# LPC1114_--_Valdez_Mutant_v_03.net
KiCad netlist of a schematic drawn in EAGLE
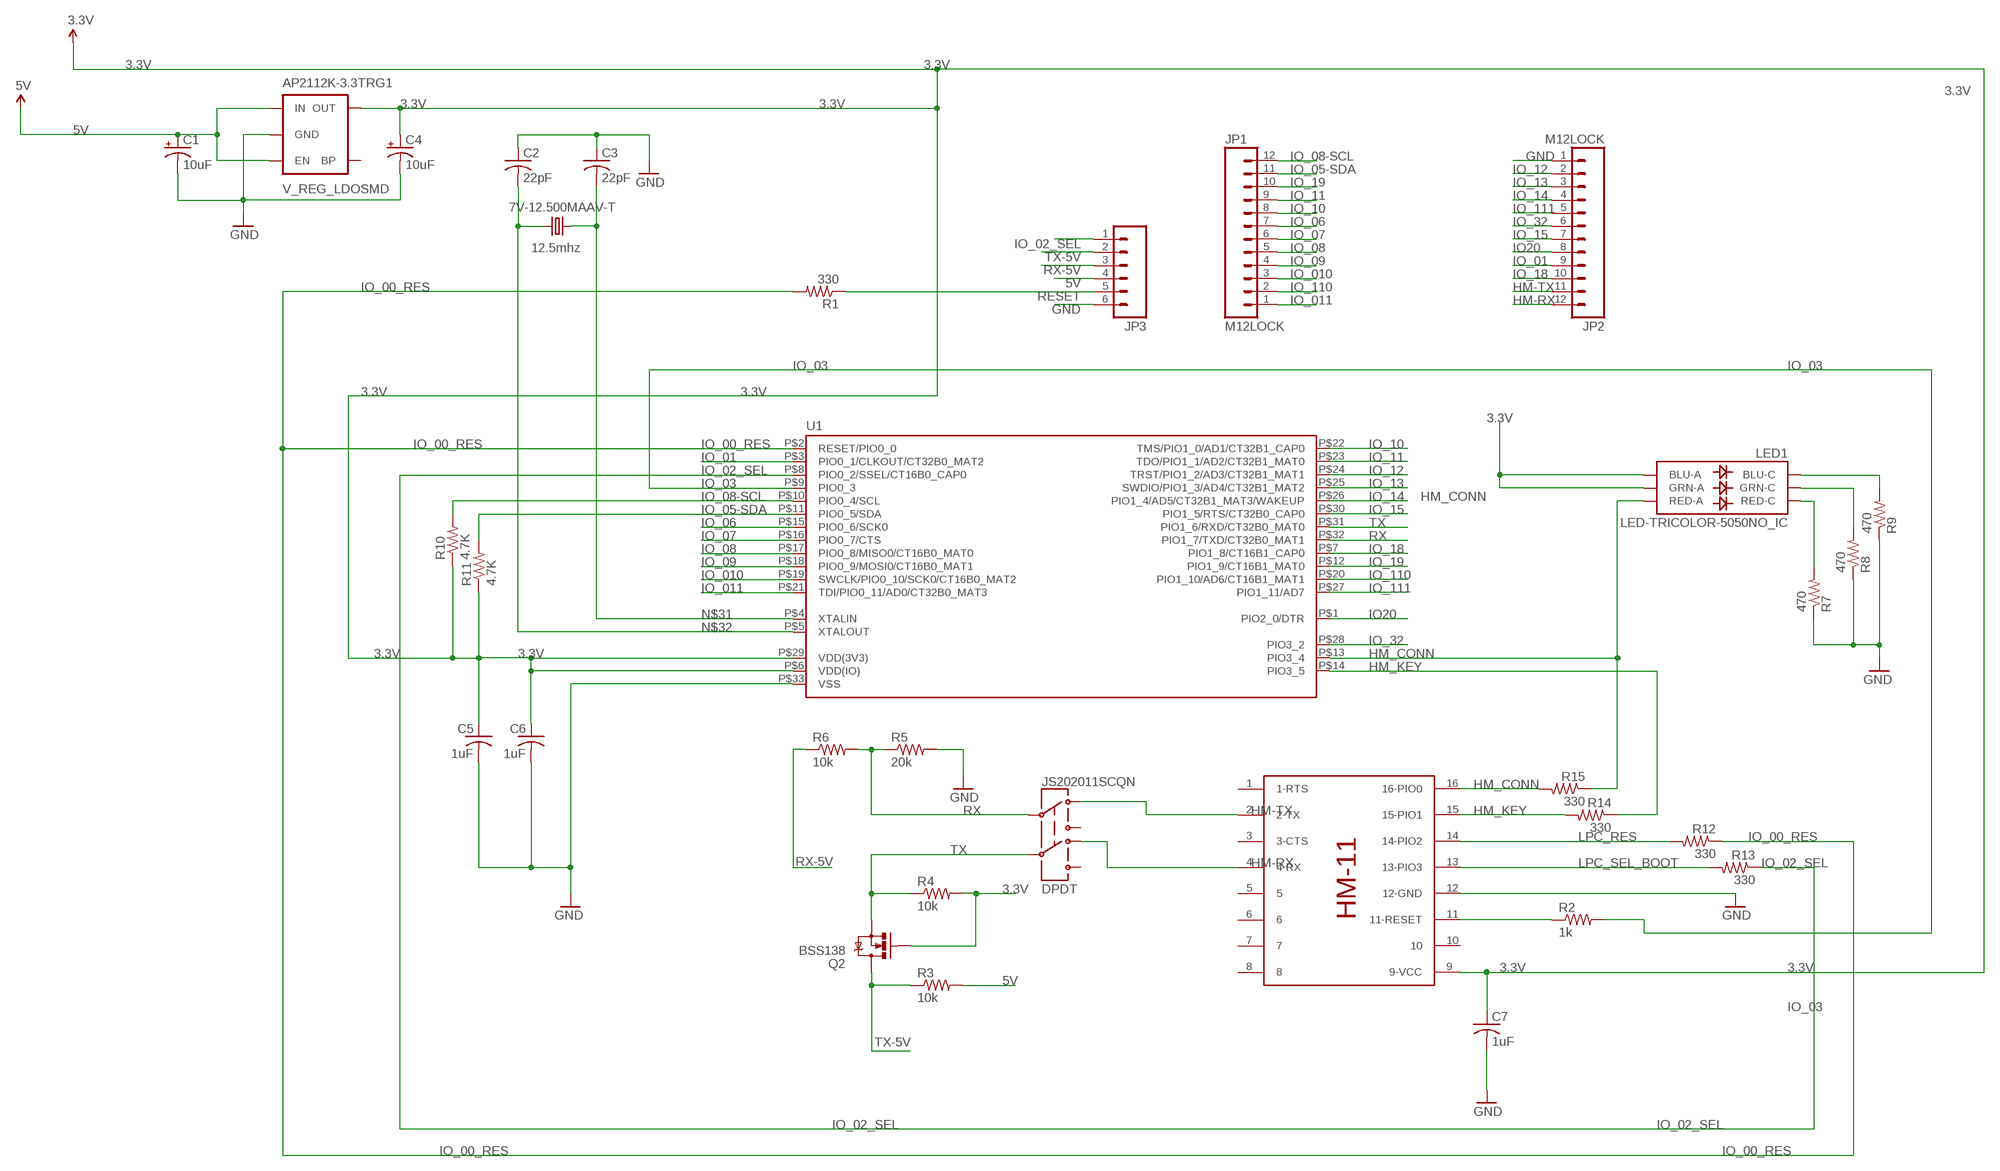
[diagram p0: schematic, sheet 1]

(export (version "E")
  (design (tool "Eeschema 10.0.6"))
  (components
    (comp (ref "7V-12.500MAAV-T")
      (value "12.5mhz")
      (footprint "eagle-import:CRYSTAL-SMD-5X3")
      (libsource (lib "eagle-import") (part "CRYSTAL5X3"))
    )
    (comp (ref "AP2112K-3.3TRG1")
      (value "V_REG_LDOSMD")
      (footprint "eagle-import:SOT23-5")
      (libsource (lib "eagle-import") (part "V_REG_LDOSMD"))
    )
    (comp (ref "C1")
      (value "10uF")
      (footprint "eagle-import:EIA3216")
      (libsource (lib "eagle-import") (part "CAP_POL1206"))
    )
    (comp (ref "C2")
      (value "22pF")
      (footprint "eagle-import:C0402K")
      (libsource (lib "eagle-import") (part "C-USC0402K"))
    )
    (comp (ref "C3")
      (value "22pF")
      (footprint "eagle-import:C0402K")
      (libsource (lib "eagle-import") (part "C-USC0402K"))
    )
    (comp (ref "C4")
      (value "10uF")
      (footprint "eagle-import:EIA3216")
      (libsource (lib "eagle-import") (part "CAP_POL1206"))
    )
    (comp (ref "C5")
      (value "1uF")
      (footprint "eagle-import:C0402K")
      (libsource (lib "eagle-import") (part "C-USC0402K"))
    )
    (comp (ref "C6")
      (value "1uF")
      (footprint "eagle-import:C0402K")
      (libsource (lib "eagle-import") (part "C-USC0402K"))
    )
    (comp (ref "C7")
      (value "1uF")
      (footprint "eagle-import:C0402K")
      (libsource (lib "eagle-import") (part "C-USC0402K"))
    )
    (comp (ref "JP1")
      (value "M12LOCK")
      (footprint "eagle-import:1X12_LOCK")
      (libsource (lib "eagle-import") (part "M12LOCK"))
    )
    (comp (ref "JP2")
      (value "M12LOCK")
      (footprint "eagle-import:1X12_LOCK")
      (libsource (lib "eagle-import") (part "M12LOCK"))
    )
    (comp (ref "JP3")
      (value "M06LOCK")
      (footprint "eagle-import:1X06_LOCK")
      (libsource (lib "eagle-import") (part "M06LOCK"))
    )
    (comp (ref "JS202011SCQN")
      (value "DPDT")
      (footprint "eagle-import:AYZ0202")
      (libsource (lib "eagle-import") (part "SWITCH-DPDTAYZ0202"))
    )
    (comp (ref "LED1")
      (value "LED-TRICOLOR-5050NO_IC")
      (footprint "eagle-import:LED-TRICOLOR-5050")
      (libsource (lib "eagle-import") (part "LED-TRICOLOR-5050NO_IC"))
    )
    (comp (ref "Q2")
      (value "BSS138")
      (footprint "eagle-import:SOT23")
      (libsource (lib "eagle-import") (part "MOSFET-NCHANNELBSS138"))
    )
    (comp (ref "R1")
      (value "330")
      (footprint "eagle-import:R0402")
      (libsource (lib "eagle-import") (part "R-US_R0402"))
    )
    (comp (ref "R2")
      (value "1k")
      (footprint "eagle-import:R0402")
      (libsource (lib "eagle-import") (part "R-US_R0402"))
    )
    (comp (ref "R3")
      (value "10k")
      (footprint "eagle-import:R0402")
      (libsource (lib "eagle-import") (part "R-US_R0402"))
    )
    (comp (ref "R4")
      (value "10k")
      (footprint "eagle-import:R0402")
      (libsource (lib "eagle-import") (part "R-US_R0402"))
    )
    (comp (ref "R5")
      (value "20k")
      (footprint "eagle-import:R0402")
      (libsource (lib "eagle-import") (part "R-US_R0402"))
    )
    (comp (ref "R6")
      (value "10k")
      (footprint "eagle-import:R0402")
      (libsource (lib "eagle-import") (part "R-US_R0402"))
    )
    (comp (ref "R7")
      (value "470")
      (footprint "eagle-import:R0402")
      (libsource (lib "eagle-import") (part "R-US_R0402"))
    )
    (comp (ref "R8")
      (value "470")
      (footprint "eagle-import:R0402")
      (libsource (lib "eagle-import") (part "R-US_R0402"))
    )
    (comp (ref "R9")
      (value "470")
      (footprint "eagle-import:R0402")
      (libsource (lib "eagle-import") (part "R-US_R0402"))
    )
    (comp (ref "R10")
      (value "4.7K")
      (footprint "eagle-import:R0402")
      (libsource (lib "eagle-import") (part "R-US_R0402"))
    )
    (comp (ref "R11")
      (value "4.7K")
      (footprint "eagle-import:R0402")
      (libsource (lib "eagle-import") (part "R-US_R0402"))
    )
    (comp (ref "R12")
      (value "330")
      (footprint "eagle-import:R0402")
      (libsource (lib "eagle-import") (part "R-US_R0402"))
    )
    (comp (ref "R13")
      (value "330")
      (footprint "eagle-import:R0402")
      (libsource (lib "eagle-import") (part "R-US_R0402"))
    )
    (comp (ref "R14")
      (value "330")
      (footprint "eagle-import:R0402")
      (libsource (lib "eagle-import") (part "R-US_R0402"))
    )
    (comp (ref "R15")
      (value "330")
      (footprint "eagle-import:R0402")
      (libsource (lib "eagle-import") (part "R-US_R0402"))
    )
    (comp (ref "U$1")
      (value "HM-11")
      (footprint "eagle-import:HM-11")
      (libsource (lib "eagle-import") (part "HM-11"))
    )
    (comp (ref "U1")
      (value "LPC1113/4_QFN")
      (footprint "eagle-import:HVQFN33-7X7")
      (fields (field (name "MANF") "NXP"))
      (libsource (lib "eagle-import") (part "LPC1113/4_QFN"))
    )
  )
  (nets
    (net (code "1") (name "/HM-RX") (class "Default")
      (node (ref "JP2") (pin "12") (pinfunction "12_12") (pintype "passive"))
      (node (ref "JS202011SCQN") (pin "4") (pinfunction "4_4") (pintype "bidirectional"))
      (node (ref "U$1") (pin "4") (pinfunction "4-RX_4") (pintype "bidirectional"))
    )
    (net (code "2") (name "/HM-TX") (class "Default")
      (node (ref "JP2") (pin "11") (pinfunction "11_11") (pintype "passive"))
      (node (ref "JS202011SCQN") (pin "1") (pinfunction "1_1") (pintype "bidirectional"))
      (node (ref "U$1") (pin "2") (pinfunction "2-TX_2") (pintype "bidirectional"))
    )
    (net (code "3") (name "/HM_CONN") (class "Default")
      (node (ref "LED1") (pin "2") (pinfunction "RED-A_2") (pintype "bidirectional"))
      (node (ref "R15") (pin "1") (pinfunction "1_1") (pintype "passive"))
      (node (ref "U1") (pin "P$13") (pinfunction "PIO3_4_P$13") (pintype "bidirectional"))
    )
    (net (code "4") (name "/HM_KEY") (class "Default")
      (node (ref "R14") (pin "1") (pinfunction "1_1") (pintype "passive"))
      (node (ref "U1") (pin "P$14") (pinfunction "PIO3_5_P$14") (pintype "bidirectional"))
    )
    (net (code "5") (name "/IO20") (class "Default")
      (node (ref "JP2") (pin "8") (pinfunction "8_8") (pintype "passive"))
      (node (ref "U1") (pin "P$1") (pinfunction "PIO2_0/DTR_P$1") (pintype "bidirectional"))
    )
    (net (code "6") (name "/IO_00_RES") (class "Default")
      (node (ref "R1") (pin "2") (pinfunction "2_2") (pintype "passive"))
      (node (ref "R12") (pin "1") (pinfunction "1_1") (pintype "passive"))
      (node (ref "U1") (pin "P$2") (pinfunction "RESET/PIO0_0_P$2") (pintype "bidirectional"))
    )
    (net (code "7") (name "/IO_01") (class "Default")
      (node (ref "JP2") (pin "9") (pinfunction "9_9") (pintype "passive"))
      (node (ref "U1") (pin "P$3") (pinfunction "PIO0_1/CLKOUT/CT32B0_MAT2_P$3") (pintype "bidirectional"))
    )
    (net (code "8") (name "/IO_02_SEL") (class "Default")
      (node (ref "JP3") (pin "1") (pinfunction "1_1") (pintype "passive"))
      (node (ref "R13") (pin "1") (pinfunction "1_1") (pintype "passive"))
      (node (ref "U1") (pin "P$8") (pinfunction "PIO0_2/SSEL/CT16B0_CAP0_P$8") (pintype "bidirectional"))
    )
    (net (code "9") (name "/IO_03") (class "Default")
      (node (ref "R2") (pin "2") (pinfunction "2_2") (pintype "passive"))
      (node (ref "U1") (pin "P$9") (pinfunction "PIO0_3_P$9") (pintype "bidirectional"))
    )
    (net (code "10") (name "/IO_05-SDA") (class "Default")
      (node (ref "JP1") (pin "11") (pinfunction "11_11") (pintype "passive"))
      (node (ref "R11") (pin "2") (pinfunction "2_2") (pintype "passive"))
      (node (ref "U1") (pin "P$11") (pinfunction "PIO0_5/SDA_P$11") (pintype "bidirectional"))
    )
    (net (code "11") (name "/IO_06") (class "Default")
      (node (ref "JP1") (pin "7") (pinfunction "7_7") (pintype "passive"))
      (node (ref "U1") (pin "P$15") (pinfunction "PIO0_6/SCK0_P$15") (pintype "bidirectional"))
    )
    (net (code "12") (name "/IO_07") (class "Default")
      (node (ref "JP1") (pin "6") (pinfunction "6_6") (pintype "passive"))
      (node (ref "U1") (pin "P$16") (pinfunction "PIO0_7/CTS_P$16") (pintype "bidirectional"))
    )
    (net (code "13") (name "/IO_08") (class "Default")
      (node (ref "JP1") (pin "5") (pinfunction "5_5") (pintype "passive"))
      (node (ref "U1") (pin "P$17") (pinfunction "PIO0_8/MISO0/CT16B0_MAT0_P$17") (pintype "bidirectional"))
    )
    (net (code "14") (name "/IO_08-SCL") (class "Default")
      (node (ref "JP1") (pin "12") (pinfunction "12_12") (pintype "passive"))
      (node (ref "R10") (pin "2") (pinfunction "2_2") (pintype "passive"))
      (node (ref "U1") (pin "P$10") (pinfunction "PIO0_4/SCL_P$10") (pintype "bidirectional"))
    )
    (net (code "15") (name "/IO_09") (class "Default")
      (node (ref "JP1") (pin "4") (pinfunction "4_4") (pintype "passive"))
      (node (ref "U1") (pin "P$18") (pinfunction "PIO0_9/MOSI0/CT16B0_MAT1_P$18") (pintype "bidirectional"))
    )
    (net (code "16") (name "/IO_10") (class "Default")
      (node (ref "JP1") (pin "8") (pinfunction "8_8") (pintype "passive"))
      (node (ref "U1") (pin "P$22") (pinfunction "TMS/PIO1_0/AD1/CT32B1_CAP0_P$22") (pintype "bidirectional"))
    )
    (net (code "17") (name "/IO_010") (class "Default")
      (node (ref "JP1") (pin "3") (pinfunction "3_3") (pintype "passive"))
      (node (ref "U1") (pin "P$19") (pinfunction "SWCLK/PIO0_10/SCK0/CT16B0_MAT2_P$19") (pintype "bidirectional"))
    )
    (net (code "18") (name "/IO_011") (class "Default")
      (node (ref "JP1") (pin "1") (pinfunction "1_1") (pintype "passive"))
      (node (ref "U1") (pin "P$21") (pinfunction "TDI/PIO0_11/AD0/CT32B0_MAT3_P$21") (pintype "bidirectional"))
    )
    (net (code "19") (name "/IO_11") (class "Default")
      (node (ref "JP1") (pin "9") (pinfunction "9_9") (pintype "passive"))
      (node (ref "U1") (pin "P$23") (pinfunction "TDO/PIO1_1/AD2/CT32B1_MAT0_P$23") (pintype "bidirectional"))
    )
    (net (code "20") (name "/IO_12") (class "Default")
      (node (ref "JP2") (pin "2") (pinfunction "2_2") (pintype "passive"))
      (node (ref "U1") (pin "P$24") (pinfunction "TRST/PIO1_2/AD3/CT32B1_MAT1_P$24") (pintype "bidirectional"))
    )
    (net (code "21") (name "/IO_13") (class "Default")
      (node (ref "JP2") (pin "3") (pinfunction "3_3") (pintype "passive"))
      (node (ref "U1") (pin "P$25") (pinfunction "SWDIO/PIO1_3/AD4/CT32B1_MAT2_P$25") (pintype "bidirectional"))
    )
    (net (code "22") (name "/IO_14") (class "Default")
      (node (ref "JP2") (pin "4") (pinfunction "4_4") (pintype "passive"))
      (node (ref "U1") (pin "P$26") (pinfunction "PIO1_4/AD5/CT32B1_MAT3/WAKEUP_P$26") (pintype "bidirectional"))
    )
    (net (code "23") (name "/IO_15") (class "Default")
      (node (ref "JP2") (pin "7") (pinfunction "7_7") (pintype "passive"))
      (node (ref "U1") (pin "P$30") (pinfunction "PIO1_5/RTS/CT32B0_CAP0_P$30") (pintype "bidirectional"))
    )
    (net (code "24") (name "/IO_18") (class "Default")
      (node (ref "JP2") (pin "10") (pinfunction "10_10") (pintype "passive"))
      (node (ref "U1") (pin "P$7") (pinfunction "PIO1_8/CT16B1_CAP0_P$7") (pintype "bidirectional"))
    )
    (net (code "25") (name "/IO_19") (class "Default")
      (node (ref "JP1") (pin "10") (pinfunction "10_10") (pintype "passive"))
      (node (ref "U1") (pin "P$12") (pinfunction "PIO1_9/CT16B1_MAT0_P$12") (pintype "bidirectional"))
    )
    (net (code "26") (name "/IO_32") (class "Default")
      (node (ref "JP2") (pin "6") (pinfunction "6_6") (pintype "passive"))
      (node (ref "U1") (pin "P$28") (pinfunction "PIO3_2_P$28") (pintype "bidirectional"))
    )
    (net (code "27") (name "/IO_110") (class "Default")
      (node (ref "JP1") (pin "2") (pinfunction "2_2") (pintype "passive"))
      (node (ref "U1") (pin "P$20") (pinfunction "PIO1_10/AD6/CT16B1_MAT1_P$20") (pintype "bidirectional"))
    )
    (net (code "28") (name "/IO_111") (class "Default")
      (node (ref "JP2") (pin "5") (pinfunction "5_5") (pintype "passive"))
      (node (ref "U1") (pin "P$27") (pinfunction "PIO1_11/AD7_P$27") (pintype "bidirectional"))
    )
    (net (code "29") (name "/LPC_RES") (class "Default")
      (node (ref "R12") (pin "2") (pinfunction "2_2") (pintype "passive"))
      (node (ref "U$1") (pin "14") (pinfunction "14-PIO2_14") (pintype "bidirectional"))
    )
    (net (code "30") (name "/LPC_SEL_BOOT") (class "Default")
      (node (ref "R13") (pin "2") (pinfunction "2_2") (pintype "passive"))
      (node (ref "U$1") (pin "13") (pinfunction "13-PIO3_13") (pintype "bidirectional"))
    )
    (net (code "31") (name "/N$31") (class "Default")
      (node (ref "7V-12.500MAAV-T") (pin "3") (pinfunction "2_3") (pintype "passive"))
      (node (ref "C3") (pin "2") (pinfunction "2_2") (pintype "passive"))
      (node (ref "U1") (pin "P$4") (pinfunction "XTALIN_P$4") (pintype "input"))
    )
    (net (code "32") (name "/N$32") (class "Default")
      (node (ref "7V-12.500MAAV-T") (pin "1") (pinfunction "1_1") (pintype "passive"))
      (node (ref "C2") (pin "2") (pinfunction "2_2") (pintype "passive"))
      (node (ref "U1") (pin "P$5") (pinfunction "XTALOUT_P$5") (pintype "output"))
    )
    (net (code "33") (name "/RESET") (class "Default")
      (node (ref "JP3") (pin "5") (pinfunction "5_5") (pintype "passive"))
      (node (ref "R1") (pin "1") (pinfunction "1_1") (pintype "passive"))
    )
    (net (code "34") (name "/RX") (class "Default")
      (node (ref "JS202011SCQN") (pin "2") (pinfunction "2_2") (pintype "bidirectional"))
      (node (ref "R5") (pin "1") (pinfunction "1_1") (pintype "passive"))
      (node (ref "R6") (pin "2") (pinfunction "2_2") (pintype "passive"))
      (node (ref "U1") (pin "P$32") (pinfunction "PIO1_7/TXD/CT32B0_MAT1_P$32") (pintype "bidirectional"))
    )
    (net (code "35") (name "/RX-5V") (class "Default")
      (node (ref "JP3") (pin "3") (pinfunction "3_3") (pintype "passive"))
      (node (ref "R6") (pin "1") (pinfunction "1_1") (pintype "passive"))
    )
    (net (code "36") (name "/TX") (class "Default")
      (node (ref "JS202011SCQN") (pin "5") (pinfunction "5_5") (pintype "bidirectional"))
      (node (ref "Q2") (pin "2") (pinfunction "S_2") (pintype "passive"))
      (node (ref "R4") (pin "1") (pinfunction "1_1") (pintype "passive"))
      (node (ref "U1") (pin "P$31") (pinfunction "PIO1_6/RXD/CT32B0_MAT0_P$31") (pintype "bidirectional"))
    )
    (net (code "37") (name "/TX-5V") (class "Default")
      (node (ref "JP3") (pin "2") (pinfunction "2_2") (pintype "passive"))
      (node (ref "Q2") (pin "3") (pinfunction "D_3") (pintype "passive"))
      (node (ref "R3") (pin "1") (pinfunction "1_1") (pintype "passive"))
    )
    (net (code "38") (name "3.3V") (class "Default")
      (node (ref "AP2112K-3.3TRG1") (pin "5") (pinfunction "OUT_5") (pintype "passive"))
      (node (ref "C4") (pin "A") (pinfunction "+_A") (pintype "passive"))
      (node (ref "C5") (pin "1") (pinfunction "1_1") (pintype "passive"))
      (node (ref "C6") (pin "1") (pinfunction "1_1") (pintype "passive"))
      (node (ref "C7") (pin "1") (pinfunction "1_1") (pintype "passive"))
      (node (ref "LED1") (pin "1") (pinfunction "GRN-A_1") (pintype "bidirectional"))
      (node (ref "LED1") (pin "3") (pinfunction "BLU-A_3") (pintype "bidirectional"))
      (node (ref "Q2") (pin "1") (pinfunction "G_1") (pintype "passive"))
      (node (ref "R10") (pin "1") (pinfunction "1_1") (pintype "passive"))
      (node (ref "R11") (pin "1") (pinfunction "1_1") (pintype "passive"))
      (node (ref "R4") (pin "2") (pinfunction "2_2") (pintype "passive"))
      (node (ref "U$1") (pin "9") (pinfunction "9-VCC_9") (pintype "bidirectional"))
      (node (ref "U1") (pin "P$29") (pinfunction "VDD(3V3)_P$29") (pintype "power_in"))
      (node (ref "U1") (pin "P$6") (pinfunction "VDD(IO)_P$6") (pintype "power_in"))
    )
    (net (code "39") (name "5V") (class "Default")
      (node (ref "AP2112K-3.3TRG1") (pin "1") (pinfunction "IN_1") (pintype "input"))
      (node (ref "AP2112K-3.3TRG1") (pin "3") (pinfunction "EN_3") (pintype "input"))
      (node (ref "C1") (pin "A") (pinfunction "+_A") (pintype "passive"))
      (node (ref "JP3") (pin "4") (pinfunction "4_4") (pintype "passive"))
      (node (ref "R3") (pin "2") (pinfunction "2_2") (pintype "passive"))
    )
    (net (code "40") (name "GND") (class "Default")
      (node (ref "AP2112K-3.3TRG1") (pin "2") (pinfunction "GND_2") (pintype "input"))
      (node (ref "C1") (pin "C") (pinfunction "-_C") (pintype "passive"))
      (node (ref "C2") (pin "1") (pinfunction "1_1") (pintype "passive"))
      (node (ref "C3") (pin "1") (pinfunction "1_1") (pintype "passive"))
      (node (ref "C4") (pin "C") (pinfunction "-_C") (pintype "passive"))
      (node (ref "C5") (pin "2") (pinfunction "2_2") (pintype "passive"))
      (node (ref "C6") (pin "2") (pinfunction "2_2") (pintype "passive"))
      (node (ref "C7") (pin "2") (pinfunction "2_2") (pintype "passive"))
      (node (ref "JP2") (pin "1") (pinfunction "1_1") (pintype "passive"))
      (node (ref "JP3") (pin "6") (pinfunction "6_6") (pintype "passive"))
      (node (ref "R5") (pin "2") (pinfunction "2_2") (pintype "passive"))
      (node (ref "R7") (pin "1") (pinfunction "1_1") (pintype "passive"))
      (node (ref "R8") (pin "1") (pinfunction "1_1") (pintype "passive"))
      (node (ref "R9") (pin "1") (pinfunction "1_1") (pintype "passive"))
      (node (ref "U$1") (pin "12") (pinfunction "12-GND_12") (pintype "bidirectional"))
      (node (ref "U1") (pin "P$33") (pinfunction "VSS_P$33") (pintype "power_in"))
    )
    (net (code "41") (name "Net-(LED1-BLU-C)") (class "Default")
      (node (ref "LED1") (pin "4") (pinfunction "BLU-C_4") (pintype "bidirectional"))
      (node (ref "R9") (pin "2") (pinfunction "2_2") (pintype "passive"))
    )
    (net (code "42") (name "Net-(LED1-GRN-C)") (class "Default")
      (node (ref "LED1") (pin "6") (pinfunction "GRN-C_6") (pintype "bidirectional"))
      (node (ref "R8") (pin "2") (pinfunction "2_2") (pintype "passive"))
    )
    (net (code "43") (name "Net-(LED1-RED-C)") (class "Default")
      (node (ref "LED1") (pin "5") (pinfunction "RED-C_5") (pintype "bidirectional"))
      (node (ref "R7") (pin "2") (pinfunction "2_2") (pintype "passive"))
    )
    (net (code "44") (name "Net-(U$1-11-RESET)") (class "Default")
      (node (ref "R2") (pin "1") (pinfunction "1_1") (pintype "passive"))
      (node (ref "U$1") (pin "11") (pinfunction "11-RESET_11") (pintype "bidirectional"))
    )
    (net (code "45") (name "Net-(U$1-15-PIO1)") (class "Default")
      (node (ref "R14") (pin "2") (pinfunction "2_2") (pintype "passive"))
      (node (ref "U$1") (pin "15") (pinfunction "15-PIO1_15") (pintype "bidirectional"))
    )
    (net (code "46") (name "Net-(U$1-16-PIO0)") (class "Default")
      (node (ref "R15") (pin "2") (pinfunction "2_2") (pintype "passive"))
      (node (ref "U$1") (pin "16") (pinfunction "16-PIO0_16") (pintype "bidirectional"))
    )
    (net (code "47") (name "unconnected-(AP2112K-3.3TRG1-BP-Pad4)") (class "Default")
      (node (ref "AP2112K-3.3TRG1") (pin "4") (pinfunction "BP_4") (pintype "input"))
    )
    (net (code "48") (name "unconnected-(JS202011SCQN-Pad3)") (class "Default")
      (node (ref "JS202011SCQN") (pin "3") (pinfunction "3_3") (pintype "bidirectional"))
    )
    (net (code "49") (name "unconnected-(JS202011SCQN-Pad6)") (class "Default")
      (node (ref "JS202011SCQN") (pin "6") (pinfunction "6_6") (pintype "bidirectional"))
    )
    (net (code "50") (name "unconnected-(U$1-1-RTS-Pad1)") (class "Default")
      (node (ref "U$1") (pin "1") (pinfunction "1-RTS_1") (pintype "bidirectional"))
    )
    (net (code "51") (name "unconnected-(U$1-3-CTS-Pad3)") (class "Default")
      (node (ref "U$1") (pin "3") (pinfunction "3-CTS_3") (pintype "bidirectional"))
    )
    (net (code "52") (name "unconnected-(U$1-Pad5)") (class "Default")
      (node (ref "U$1") (pin "5") (pinfunction "5_5") (pintype "bidirectional"))
    )
    (net (code "53") (name "unconnected-(U$1-Pad6)") (class "Default")
      (node (ref "U$1") (pin "6") (pinfunction "6_6") (pintype "bidirectional"))
    )
    (net (code "54") (name "unconnected-(U$1-Pad7)") (class "Default")
      (node (ref "U$1") (pin "7") (pinfunction "7_7") (pintype "bidirectional"))
    )
    (net (code "55") (name "unconnected-(U$1-Pad8)") (class "Default")
      (node (ref "U$1") (pin "8") (pinfunction "8_8") (pintype "bidirectional"))
    )
    (net (code "56") (name "unconnected-(U$1-Pad10)") (class "Default")
      (node (ref "U$1") (pin "10") (pinfunction "10_10") (pintype "bidirectional"))
    )
  )
)
